# wemos-br1-board.net
KiCad netlist of a schematic drawn in EAGLE
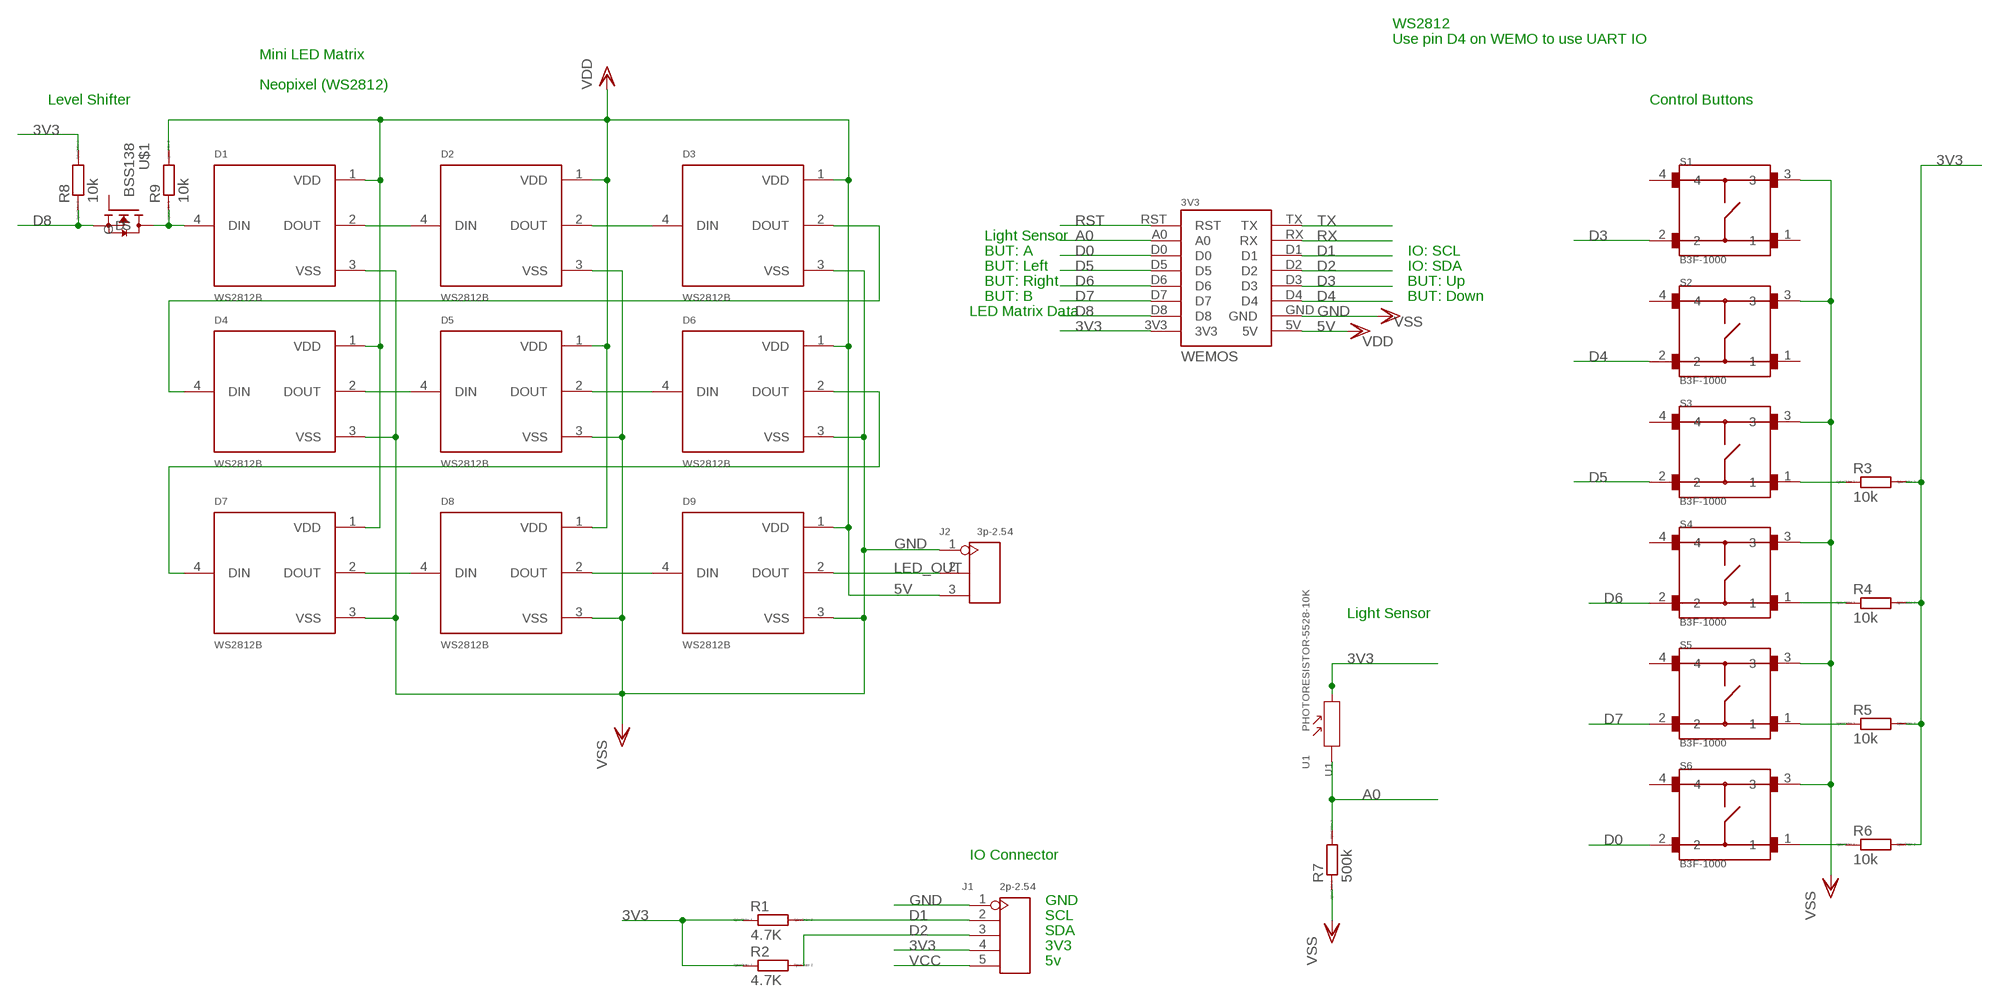
[diagram p0: schematic, sheet 1]

(export (version "E")
  (design (tool "Eeschema 10.0.6"))
  (components
    (comp (ref "3V3")
      (value "WEMOS")
      (footprint "eagle-import:WEMOS")
      (libsource (lib "eagle-import") (part "WEMOS"))
    )
    (comp (ref "D1")
      (value "WS2812B")
      (footprint "eagle-import:LED_WS2812B")
      (fields (field (name "MF") "Adafruit Industries"))
      (libsource (lib "eagle-import") (part "WS2812B"))
    )
    (comp (ref "D2")
      (value "WS2812B")
      (footprint "eagle-import:LED_WS2812B")
      (fields (field (name "MF") "Adafruit Industries"))
      (libsource (lib "eagle-import") (part "WS2812B"))
    )
    (comp (ref "D3")
      (value "WS2812B")
      (footprint "eagle-import:LED_WS2812B")
      (fields (field (name "MF") "Adafruit Industries"))
      (libsource (lib "eagle-import") (part "WS2812B"))
    )
    (comp (ref "D4")
      (value "WS2812B")
      (footprint "eagle-import:LED_WS2812B")
      (fields (field (name "MF") "Adafruit Industries"))
      (libsource (lib "eagle-import") (part "WS2812B"))
    )
    (comp (ref "D5")
      (value "WS2812B")
      (footprint "eagle-import:LED_WS2812B")
      (fields (field (name "MF") "Adafruit Industries"))
      (libsource (lib "eagle-import") (part "WS2812B"))
    )
    (comp (ref "D6")
      (value "WS2812B")
      (footprint "eagle-import:LED_WS2812B")
      (fields (field (name "MF") "Adafruit Industries"))
      (libsource (lib "eagle-import") (part "WS2812B"))
    )
    (comp (ref "D7")
      (value "WS2812B")
      (footprint "eagle-import:LED_WS2812B")
      (fields (field (name "MF") "Adafruit Industries"))
      (libsource (lib "eagle-import") (part "WS2812B"))
    )
    (comp (ref "D8")
      (value "WS2812B")
      (footprint "eagle-import:LED_WS2812B")
      (fields (field (name "MF") "Adafruit Industries"))
      (libsource (lib "eagle-import") (part "WS2812B"))
    )
    (comp (ref "D9")
      (value "WS2812B")
      (footprint "eagle-import:LED_WS2812B")
      (fields (field (name "MF") "Adafruit Industries"))
      (libsource (lib "eagle-import") (part "WS2812B"))
    )
    (comp (ref "J1")
      (value "2p-2.54")
      (footprint "eagle-import:H5-2.54")
      (libsource (lib "eagle-import") (part "DIP-BLACK-MALE-HEADER-VERT(5P-2.54)"))
    )
    (comp (ref "J2")
      (value "3p-2.54")
      (footprint "eagle-import:H3-2.54")
      (fields (field (name "MPN") "F185-1103A0BSYA1"))
      (libsource (lib "eagle-import") (part "DIP-BLACK-FEMALE-HEADER-VERT(3P-2.54)"))
    )
    (comp (ref "R1")
      (value "4.7K")
      (footprint "eagle-import:R0805")
      (libsource (lib "eagle-import") (part "R"))
    )
    (comp (ref "R2")
      (value "4.7K")
      (footprint "eagle-import:R0805")
      (libsource (lib "eagle-import") (part "R"))
    )
    (comp (ref "R3")
      (value "10k")
      (footprint "eagle-import:R0805")
      (libsource (lib "eagle-import") (part "R"))
    )
    (comp (ref "R4")
      (value "10k")
      (footprint "eagle-import:R0805")
      (libsource (lib "eagle-import") (part "R"))
    )
    (comp (ref "R5")
      (value "10k")
      (footprint "eagle-import:R0805")
      (libsource (lib "eagle-import") (part "R"))
    )
    (comp (ref "R6")
      (value "10k")
      (footprint "eagle-import:R0805")
      (libsource (lib "eagle-import") (part "R"))
    )
    (comp (ref "R7")
      (value "500k")
      (footprint "eagle-import:R0805")
      (libsource (lib "eagle-import") (part "R"))
    )
    (comp (ref "R8")
      (value "10k")
      (footprint "eagle-import:R0805")
      (libsource (lib "eagle-import") (part "R"))
    )
    (comp (ref "R9")
      (value "10k")
      (footprint "eagle-import:R0805")
      (libsource (lib "eagle-import") (part "R"))
    )
    (comp (ref "S1")
      (value "B3F-1000")
      (footprint "eagle-import:SW_B3F-1000")
      (fields (field (name "MF") "Omron"))
      (libsource (lib "eagle-import") (part "B3F-1000"))
    )
    (comp (ref "S2")
      (value "B3F-1000")
      (footprint "eagle-import:SW_B3F-1000")
      (fields (field (name "MF") "Omron"))
      (libsource (lib "eagle-import") (part "B3F-1000"))
    )
    (comp (ref "S3")
      (value "B3F-1000")
      (footprint "eagle-import:SW_B3F-1000")
      (fields (field (name "MF") "Omron"))
      (libsource (lib "eagle-import") (part "B3F-1000"))
    )
    (comp (ref "S4")
      (value "B3F-1000")
      (footprint "eagle-import:SW_B3F-1000")
      (fields (field (name "MF") "Omron"))
      (libsource (lib "eagle-import") (part "B3F-1000"))
    )
    (comp (ref "S5")
      (value "B3F-1000")
      (footprint "eagle-import:SW_B3F-1000")
      (fields (field (name "MF") "Omron"))
      (libsource (lib "eagle-import") (part "B3F-1000"))
    )
    (comp (ref "S6")
      (value "B3F-1000")
      (footprint "eagle-import:SW_B3F-1000")
      (fields (field (name "MF") "Omron"))
      (libsource (lib "eagle-import") (part "B3F-1000"))
    )
    (comp (ref "U$1")
      (value "BSS138")
      (footprint "eagle-import:BSS138")
      (fields (field (name "MF") "Fairchild Semiconductor"))
      (libsource (lib "eagle-import") (part "BSS138"))
    )
    (comp (ref "U1")
      (value "PHOTORESISTOR-5528-10K")
      (footprint "eagle-import:SNR2-3.0")
      (libsource (lib "eagle-import") (part "PHOTORESISTOR-5528-10K(2P-5.0X4.2MM)"))
    )
  )
  (nets
    (net (code "1") (name "/3V3") (class "Default")
      (node (ref "3V3") (pin "3V3") (pinfunction "3V3_3V3") (pintype "bidirectional"))
      (node (ref "J1") (pin "4") (pinfunction "4_4") (pintype "bidirectional"))
      (node (ref "R1") (pin "1") (pinfunction "1_1") (pintype "passive"))
      (node (ref "R2") (pin "1") (pinfunction "1_1") (pintype "passive"))
      (node (ref "R3") (pin "2") (pinfunction "2_2") (pintype "passive"))
      (node (ref "R4") (pin "2") (pinfunction "2_2") (pintype "passive"))
      (node (ref "R5") (pin "2") (pinfunction "2_2") (pintype "passive"))
      (node (ref "R6") (pin "2") (pinfunction "2_2") (pintype "passive"))
      (node (ref "R8") (pin "2") (pinfunction "2_2") (pintype "passive"))
      (node (ref "U1") (pin "2") (pinfunction "P$2_2") (pintype "bidirectional"))
    )
    (net (code "2") (name "/A0") (class "Default")
      (node (ref "3V3") (pin "A0") (pinfunction "A0_A0") (pintype "bidirectional"))
      (node (ref "R7") (pin "2") (pinfunction "2_2") (pintype "passive"))
      (node (ref "U1") (pin "1") (pinfunction "P$1_1") (pintype "bidirectional"))
    )
    (net (code "3") (name "/D0") (class "Default")
      (node (ref "3V3") (pin "D0") (pinfunction "D0_D0") (pintype "bidirectional"))
      (node (ref "S6") (pin "2") (pinfunction "2_2") (pintype "passive"))
    )
    (net (code "4") (name "/D1") (class "Default")
      (node (ref "3V3") (pin "D1") (pinfunction "D1_D1") (pintype "bidirectional"))
      (node (ref "J1") (pin "2") (pinfunction "2_2") (pintype "bidirectional"))
      (node (ref "R1") (pin "2") (pinfunction "2_2") (pintype "passive"))
    )
    (net (code "5") (name "/D2") (class "Default")
      (node (ref "3V3") (pin "D2") (pinfunction "D2_D2") (pintype "bidirectional"))
      (node (ref "J1") (pin "3") (pinfunction "3_3") (pintype "bidirectional"))
      (node (ref "R2") (pin "2") (pinfunction "2_2") (pintype "passive"))
    )
    (net (code "6") (name "/D3") (class "Default")
      (node (ref "3V3") (pin "D3") (pinfunction "D3_D3") (pintype "bidirectional"))
      (node (ref "S1") (pin "2") (pinfunction "2_2") (pintype "passive"))
    )
    (net (code "7") (name "/D4") (class "Default")
      (node (ref "3V3") (pin "D4") (pinfunction "D4_D4") (pintype "bidirectional"))
      (node (ref "S2") (pin "2") (pinfunction "2_2") (pintype "passive"))
    )
    (net (code "8") (name "/D5") (class "Default")
      (node (ref "3V3") (pin "D5") (pinfunction "D5_D5") (pintype "bidirectional"))
      (node (ref "S3") (pin "2") (pinfunction "2_2") (pintype "passive"))
    )
    (net (code "9") (name "/D6") (class "Default")
      (node (ref "3V3") (pin "D6") (pinfunction "D6_D6") (pintype "bidirectional"))
      (node (ref "S4") (pin "2") (pinfunction "2_2") (pintype "passive"))
    )
    (net (code "10") (name "/D7") (class "Default")
      (node (ref "3V3") (pin "D7") (pinfunction "D7_D7") (pintype "bidirectional"))
      (node (ref "S5") (pin "2") (pinfunction "2_2") (pintype "passive"))
    )
    (net (code "11") (name "/D8") (class "Default")
      (node (ref "3V3") (pin "D8") (pinfunction "D8_D8") (pintype "bidirectional"))
      (node (ref "R8") (pin "1") (pinfunction "1_1") (pintype "passive"))
      (node (ref "U$1") (pin "S") (pinfunction "S_S") (pintype "passive"))
    )
    (net (code "12") (name "/LED_OUT") (class "Default")
      (node (ref "D9") (pin "2") (pinfunction "DOUT_2") (pintype "output"))
      (node (ref "J2") (pin "2") (pinfunction "P$2_2") (pintype "bidirectional"))
    )
    (net (code "13") (name "/RST") (class "Default")
      (node (ref "3V3") (pin "RST") (pinfunction "RST_RST") (pintype "bidirectional"))
    )
    (net (code "14") (name "/RX") (class "Default")
      (node (ref "3V3") (pin "RX") (pinfunction "RX_RX") (pintype "bidirectional"))
    )
    (net (code "15") (name "/TX") (class "Default")
      (node (ref "3V3") (pin "TX") (pinfunction "TX_TX") (pintype "bidirectional"))
    )
    (net (code "16") (name "/VCC") (class "Default")
      (node (ref "J1") (pin "5") (pinfunction "5_5") (pintype "bidirectional"))
    )
    (net (code "17") (name "Net-(D1-DIN)") (class "Default")
      (node (ref "D1") (pin "4") (pinfunction "DIN_4") (pintype "input"))
      (node (ref "R9") (pin "1") (pinfunction "1_1") (pintype "passive"))
      (node (ref "U$1") (pin "D") (pinfunction "D_D") (pintype "passive"))
    )
    (net (code "18") (name "Net-(D1-DOUT)") (class "Default")
      (node (ref "D1") (pin "2") (pinfunction "DOUT_2") (pintype "output"))
      (node (ref "D2") (pin "4") (pinfunction "DIN_4") (pintype "input"))
    )
    (net (code "19") (name "Net-(D2-DOUT)") (class "Default")
      (node (ref "D2") (pin "2") (pinfunction "DOUT_2") (pintype "output"))
      (node (ref "D3") (pin "4") (pinfunction "DIN_4") (pintype "input"))
    )
    (net (code "20") (name "Net-(D3-DOUT)") (class "Default")
      (node (ref "D3") (pin "2") (pinfunction "DOUT_2") (pintype "output"))
      (node (ref "D4") (pin "4") (pinfunction "DIN_4") (pintype "input"))
    )
    (net (code "21") (name "Net-(D4-DOUT)") (class "Default")
      (node (ref "D4") (pin "2") (pinfunction "DOUT_2") (pintype "output"))
      (node (ref "D5") (pin "4") (pinfunction "DIN_4") (pintype "input"))
    )
    (net (code "22") (name "Net-(D5-DOUT)") (class "Default")
      (node (ref "D5") (pin "2") (pinfunction "DOUT_2") (pintype "output"))
      (node (ref "D6") (pin "4") (pinfunction "DIN_4") (pintype "input"))
    )
    (net (code "23") (name "Net-(D6-DOUT)") (class "Default")
      (node (ref "D6") (pin "2") (pinfunction "DOUT_2") (pintype "output"))
      (node (ref "D7") (pin "4") (pinfunction "DIN_4") (pintype "input"))
    )
    (net (code "24") (name "Net-(D7-DOUT)") (class "Default")
      (node (ref "D7") (pin "2") (pinfunction "DOUT_2") (pintype "output"))
      (node (ref "D8") (pin "4") (pinfunction "DIN_4") (pintype "input"))
    )
    (net (code "25") (name "Net-(D8-DOUT)") (class "Default")
      (node (ref "D8") (pin "2") (pinfunction "DOUT_2") (pintype "output"))
      (node (ref "D9") (pin "4") (pinfunction "DIN_4") (pintype "input"))
    )
    (net (code "26") (name "Net-(R3-Pad1)") (class "Default")
      (node (ref "R3") (pin "1") (pinfunction "1_1") (pintype "passive"))
      (node (ref "S3") (pin "1") (pinfunction "1_1") (pintype "passive"))
    )
    (net (code "27") (name "Net-(R4-Pad1)") (class "Default")
      (node (ref "R4") (pin "1") (pinfunction "1_1") (pintype "passive"))
      (node (ref "S4") (pin "1") (pinfunction "1_1") (pintype "passive"))
    )
    (net (code "28") (name "Net-(R5-Pad1)") (class "Default")
      (node (ref "R5") (pin "1") (pinfunction "1_1") (pintype "passive"))
      (node (ref "S5") (pin "1") (pinfunction "1_1") (pintype "passive"))
    )
    (net (code "29") (name "Net-(R6-Pad1)") (class "Default")
      (node (ref "R6") (pin "1") (pinfunction "1_1") (pintype "passive"))
      (node (ref "S6") (pin "1") (pinfunction "1_1") (pintype "passive"))
    )
    (net (code "30") (name "VDD") (class "Default")
      (node (ref "3V3") (pin "5V") (pinfunction "5V_5V") (pintype "bidirectional"))
      (node (ref "D1") (pin "1") (pinfunction "VDD_1") (pintype "power_in"))
      (node (ref "D2") (pin "1") (pinfunction "VDD_1") (pintype "power_in"))
      (node (ref "D3") (pin "1") (pinfunction "VDD_1") (pintype "power_in"))
      (node (ref "D4") (pin "1") (pinfunction "VDD_1") (pintype "power_in"))
      (node (ref "D5") (pin "1") (pinfunction "VDD_1") (pintype "power_in"))
      (node (ref "D6") (pin "1") (pinfunction "VDD_1") (pintype "power_in"))
      (node (ref "D7") (pin "1") (pinfunction "VDD_1") (pintype "power_in"))
      (node (ref "D8") (pin "1") (pinfunction "VDD_1") (pintype "power_in"))
      (node (ref "D9") (pin "1") (pinfunction "VDD_1") (pintype "power_in"))
      (node (ref "J2") (pin "3") (pinfunction "P$3_3") (pintype "bidirectional"))
      (node (ref "R9") (pin "2") (pinfunction "2_2") (pintype "passive"))
    )
    (net (code "31") (name "VSS") (class "Default")
      (node (ref "3V3") (pin "GND") (pinfunction "GND_GND") (pintype "bidirectional"))
      (node (ref "D1") (pin "3") (pinfunction "VSS_3") (pintype "passive"))
      (node (ref "D2") (pin "3") (pinfunction "VSS_3") (pintype "passive"))
      (node (ref "D3") (pin "3") (pinfunction "VSS_3") (pintype "passive"))
      (node (ref "D4") (pin "3") (pinfunction "VSS_3") (pintype "passive"))
      (node (ref "D5") (pin "3") (pinfunction "VSS_3") (pintype "passive"))
      (node (ref "D6") (pin "3") (pinfunction "VSS_3") (pintype "passive"))
      (node (ref "D7") (pin "3") (pinfunction "VSS_3") (pintype "passive"))
      (node (ref "D8") (pin "3") (pinfunction "VSS_3") (pintype "passive"))
      (node (ref "D9") (pin "3") (pinfunction "VSS_3") (pintype "passive"))
      (node (ref "J1") (pin "1") (pinfunction "1_1") (pintype "bidirectional"))
      (node (ref "J2") (pin "1") (pinfunction "P$1_1") (pintype "bidirectional"))
      (node (ref "R7") (pin "1") (pinfunction "1_1") (pintype "passive"))
      (node (ref "S1") (pin "3") (pinfunction "3_3") (pintype "passive"))
      (node (ref "S2") (pin "3") (pinfunction "3_3") (pintype "passive"))
      (node (ref "S3") (pin "3") (pinfunction "3_3") (pintype "passive"))
      (node (ref "S4") (pin "3") (pinfunction "3_3") (pintype "passive"))
      (node (ref "S5") (pin "3") (pinfunction "3_3") (pintype "passive"))
      (node (ref "S6") (pin "3") (pinfunction "3_3") (pintype "passive"))
    )
    (net (code "32") (name "unconnected-(S1-Pad1)") (class "Default")
      (node (ref "S1") (pin "1") (pinfunction "1_1") (pintype "passive"))
    )
    (net (code "33") (name "unconnected-(S1-Pad4)") (class "Default")
      (node (ref "S1") (pin "4") (pinfunction "4_4") (pintype "passive"))
    )
    (net (code "34") (name "unconnected-(S2-Pad1)") (class "Default")
      (node (ref "S2") (pin "1") (pinfunction "1_1") (pintype "passive"))
    )
    (net (code "35") (name "unconnected-(S2-Pad4)") (class "Default")
      (node (ref "S2") (pin "4") (pinfunction "4_4") (pintype "passive"))
    )
    (net (code "36") (name "unconnected-(S3-Pad4)") (class "Default")
      (node (ref "S3") (pin "4") (pinfunction "4_4") (pintype "passive"))
    )
    (net (code "37") (name "unconnected-(S4-Pad4)") (class "Default")
      (node (ref "S4") (pin "4") (pinfunction "4_4") (pintype "passive"))
    )
    (net (code "38") (name "unconnected-(S5-Pad4)") (class "Default")
      (node (ref "S5") (pin "4") (pinfunction "4_4") (pintype "passive"))
    )
    (net (code "39") (name "unconnected-(S6-Pad4)") (class "Default")
      (node (ref "S6") (pin "4") (pinfunction "4_4") (pintype "passive"))
    )
    (net (code "40") (name "unconnected-(U$1-PadG)") (class "Default")
      (node (ref "U$1") (pin "G") (pinfunction "G_G") (pintype "passive"))
    )
  )
)
